# valve_adapter-OSH.net
KiCad netlist of a schematic drawn in EAGLE
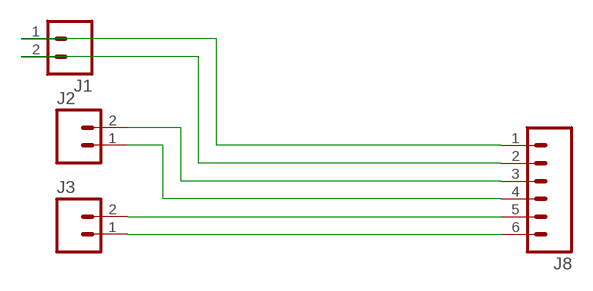
[diagram p0: schematic, sheet 1]

(export (version "E")
  (design (tool "Eeschema 10.0.6"))
  (components
    (comp (ref "J1")
      (value "M025MM")
      (footprint "eagle-import:SCREWTERMINAL-5MM-2")
      (libsource (lib "eagle-import") (part "M025MM"))
    )
    (comp (ref "J2")
      (value "M025MM")
      (footprint "eagle-import:SCREWTERMINAL-5MM-2")
      (libsource (lib "eagle-import") (part "M025MM"))
    )
    (comp (ref "J3")
      (value "M025MM")
      (footprint "eagle-import:SCREWTERMINAL-5MM-2")
      (libsource (lib "eagle-import") (part "M025MM"))
    )
    (comp (ref "J8")
      (value "M06LOCK_LONGPADS")
      (footprint "eagle-import:1X06_LOCK_LONGPADS")
      (libsource (lib "eagle-import") (part "M06LOCK_LONGPADS"))
    )
  )
  (nets
    (net (code "1") (name "Net-(J1-Pad1)") (class "Default")
      (node (ref "J1") (pin "1") (pinfunction "1_1") (pintype "passive"))
      (node (ref "J8") (pin "1") (pinfunction "1_1") (pintype "passive"))
    )
    (net (code "2") (name "Net-(J1-Pad2)") (class "Default")
      (node (ref "J1") (pin "2") (pinfunction "2_2") (pintype "passive"))
      (node (ref "J8") (pin "2") (pinfunction "2_2") (pintype "passive"))
    )
    (net (code "3") (name "Net-(J2-Pad1)") (class "Default")
      (node (ref "J2") (pin "1") (pinfunction "1_1") (pintype "passive"))
      (node (ref "J8") (pin "4") (pinfunction "4_4") (pintype "passive"))
    )
    (net (code "4") (name "Net-(J2-Pad2)") (class "Default")
      (node (ref "J2") (pin "2") (pinfunction "2_2") (pintype "passive"))
      (node (ref "J8") (pin "3") (pinfunction "3_3") (pintype "passive"))
    )
    (net (code "5") (name "Net-(J3-Pad1)") (class "Default")
      (node (ref "J3") (pin "1") (pinfunction "1_1") (pintype "passive"))
      (node (ref "J8") (pin "6") (pinfunction "6_6") (pintype "passive"))
    )
    (net (code "6") (name "Net-(J3-Pad2)") (class "Default")
      (node (ref "J3") (pin "2") (pinfunction "2_2") (pintype "passive"))
      (node (ref "J8") (pin "5") (pinfunction "5_5") (pintype "passive"))
    )
  )
)
